# J4.net
KiCad netlist of a schematic drawn in Altium Designer
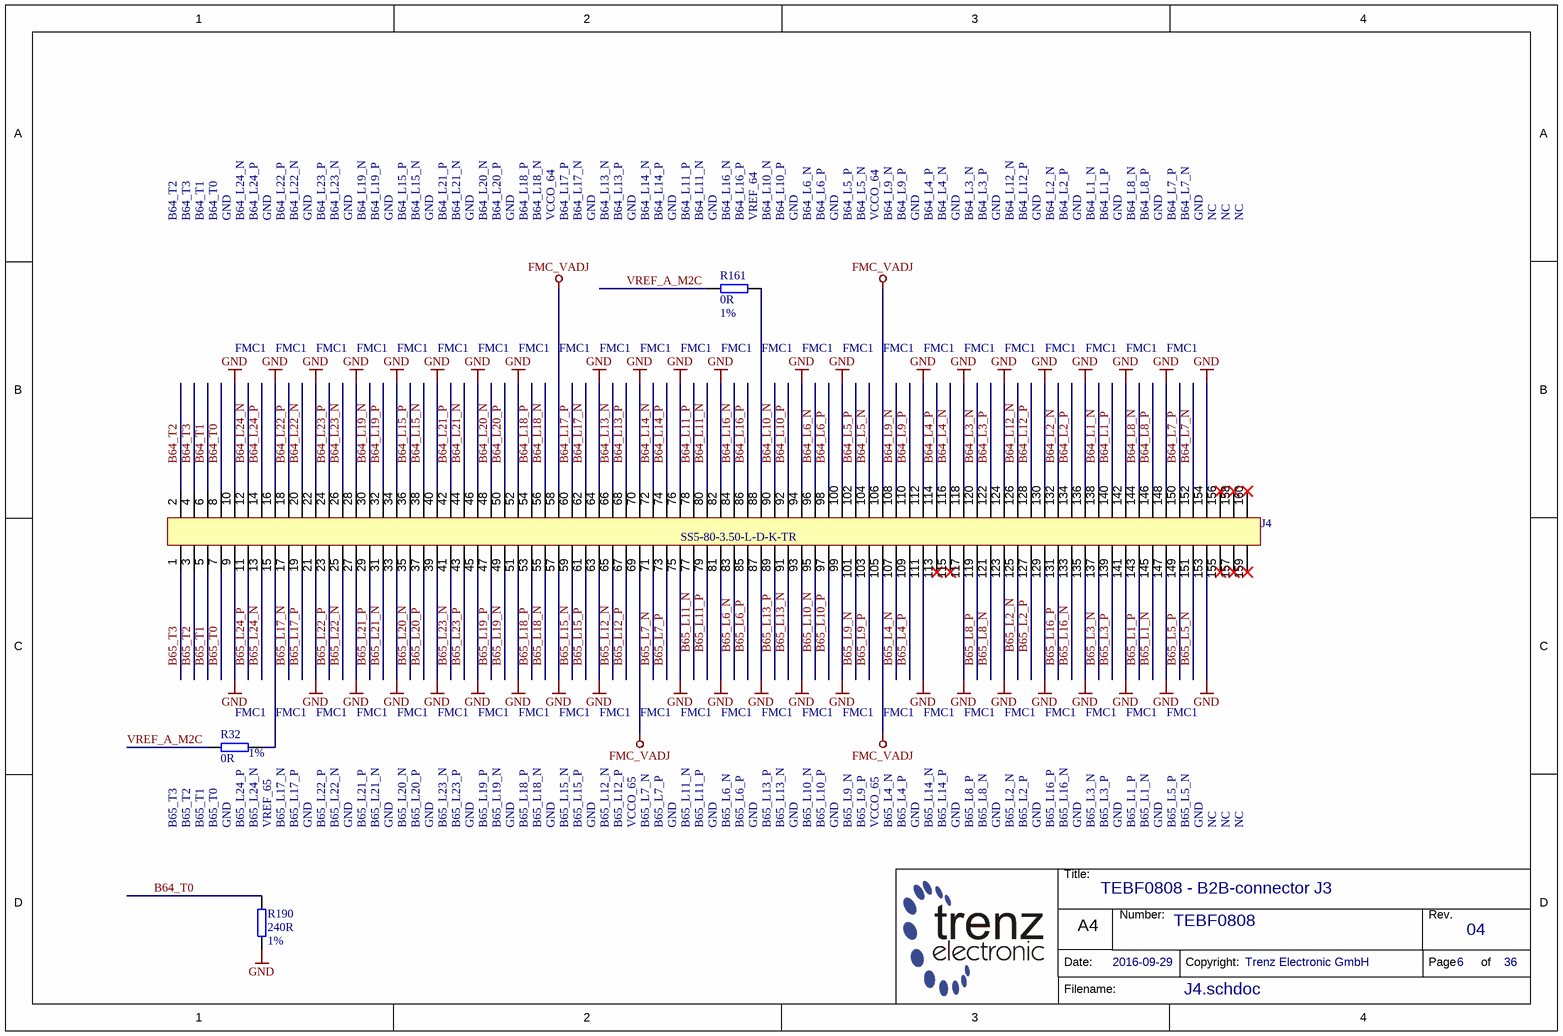
[diagram p0: J4.schdoc]

(export (version "E")
  (design (tool "Eeschema 10.0.6"))
  (components
    (comp (ref "J4")
      (value "SS5-80-3.50-L-D-K-TR")
      (footprint "SS5-80-3.50-L-D-K-TR")
      (description "Samtec Ultra Fine Pitch Socket REF192552-01, 160 Pins")
      (libsource (lib "TE") (part "CON-160"))
    )
    (comp (ref "R32")
      (value "0R")
      (footprint "RESC1005X40N")
      (description "WID SMD 0R")
      (fields (field (name "TOLERANCE") "1%"))
      (libsource (lib "TE") (part "RES"))
    )
    (comp (ref "R161")
      (value "0R")
      (footprint "RESC1005X40N")
      (description "WID SMD 0R")
      (fields (field (name "TOLERANCE") "1%"))
      (libsource (lib "TE") (part "RES"))
    )
    (comp (ref "R190")
      (value "240R")
      (footprint "RESC1005X40N")
      (description "WID SMD 240R 1% 0,063W")
      (fields (field (name "TOLERANCE") "1%"))
      (libsource (lib "TE") (part "RES"))
    )
  )
  (nets
    (net (code "1") (name "/B64_L1_N") (class "Default")
      (node (ref "J4") (pin "138") (pinfunction "138_138") (pintype "passive"))
    )
    (net (code "2") (name "/B64_L1_P") (class "Default")
      (node (ref "J4") (pin "140") (pinfunction "140_140") (pintype "passive"))
    )
    (net (code "3") (name "/B64_L2_N") (class "Default")
      (node (ref "J4") (pin "132") (pinfunction "132_132") (pintype "passive"))
    )
    (net (code "4") (name "/B64_L2_P") (class "Default")
      (node (ref "J4") (pin "134") (pinfunction "134_134") (pintype "passive"))
    )
    (net (code "5") (name "/B64_L3_N") (class "Default")
      (node (ref "J4") (pin "120") (pinfunction "120_120") (pintype "passive"))
    )
    (net (code "6") (name "/B64_L3_P") (class "Default")
      (node (ref "J4") (pin "122") (pinfunction "122_122") (pintype "passive"))
    )
    (net (code "7") (name "/B64_L4_N") (class "Default")
      (node (ref "J4") (pin "116") (pinfunction "116_116") (pintype "passive"))
    )
    (net (code "8") (name "/B64_L4_P") (class "Default")
      (node (ref "J4") (pin "114") (pinfunction "114_114") (pintype "passive"))
    )
    (net (code "9") (name "/B64_L5_N") (class "Default")
      (node (ref "J4") (pin "104") (pinfunction "104_104") (pintype "passive"))
    )
    (net (code "10") (name "/B64_L5_P") (class "Default")
      (node (ref "J4") (pin "102") (pinfunction "102_102") (pintype "passive"))
    )
    (net (code "11") (name "/B64_L6_N") (class "Default")
      (node (ref "J4") (pin "96") (pinfunction "96_96") (pintype "passive"))
    )
    (net (code "12") (name "/B64_L6_P") (class "Default")
      (node (ref "J4") (pin "98") (pinfunction "98_98") (pintype "passive"))
    )
    (net (code "13") (name "/B64_L7_N") (class "Default")
      (node (ref "J4") (pin "152") (pinfunction "152_152") (pintype "passive"))
    )
    (net (code "14") (name "/B64_L7_P") (class "Default")
      (node (ref "J4") (pin "150") (pinfunction "150_150") (pintype "passive"))
    )
    (net (code "15") (name "/B64_L8_N") (class "Default")
      (node (ref "J4") (pin "144") (pinfunction "144_144") (pintype "passive"))
    )
    (net (code "16") (name "/B64_L8_P") (class "Default")
      (node (ref "J4") (pin "146") (pinfunction "146_146") (pintype "passive"))
    )
    (net (code "17") (name "/B64_L9_N") (class "Default")
      (node (ref "J4") (pin "108") (pinfunction "108_108") (pintype "passive"))
    )
    (net (code "18") (name "/B64_L9_P") (class "Default")
      (node (ref "J4") (pin "110") (pinfunction "110_110") (pintype "passive"))
    )
    (net (code "19") (name "/B64_L10_N") (class "Default")
      (node (ref "J4") (pin "90") (pinfunction "90_90") (pintype "passive"))
    )
    (net (code "20") (name "/B64_L10_P") (class "Default")
      (node (ref "J4") (pin "92") (pinfunction "92_92") (pintype "passive"))
    )
    (net (code "21") (name "/B64_L11_N") (class "Default")
      (node (ref "J4") (pin "80") (pinfunction "80_80") (pintype "passive"))
    )
    (net (code "22") (name "/B64_L11_P") (class "Default")
      (node (ref "J4") (pin "78") (pinfunction "78_78") (pintype "passive"))
    )
    (net (code "23") (name "/B64_L12_N") (class "Default")
      (node (ref "J4") (pin "126") (pinfunction "126_126") (pintype "passive"))
    )
    (net (code "24") (name "/B64_L12_P") (class "Default")
      (node (ref "J4") (pin "128") (pinfunction "128_128") (pintype "passive"))
    )
    (net (code "25") (name "/B64_L13_N") (class "Default")
      (node (ref "J4") (pin "66") (pinfunction "66_66") (pintype "passive"))
    )
    (net (code "26") (name "/B64_L13_P") (class "Default")
      (node (ref "J4") (pin "68") (pinfunction "68_68") (pintype "passive"))
    )
    (net (code "27") (name "/B64_L14_N") (class "Default")
      (node (ref "J4") (pin "72") (pinfunction "72_72") (pintype "passive"))
    )
    (net (code "28") (name "/B64_L14_P") (class "Default")
      (node (ref "J4") (pin "74") (pinfunction "74_74") (pintype "passive"))
    )
    (net (code "29") (name "/B64_L15_N") (class "Default")
      (node (ref "J4") (pin "38") (pinfunction "38_38") (pintype "passive"))
    )
    (net (code "30") (name "/B64_L15_P") (class "Default")
      (node (ref "J4") (pin "36") (pinfunction "36_36") (pintype "passive"))
    )
    (net (code "31") (name "/B64_L16_N") (class "Default")
      (node (ref "J4") (pin "84") (pinfunction "84_84") (pintype "passive"))
    )
    (net (code "32") (name "/B64_L16_P") (class "Default")
      (node (ref "J4") (pin "86") (pinfunction "86_86") (pintype "passive"))
    )
    (net (code "33") (name "/B64_L17_N") (class "Default")
      (node (ref "J4") (pin "62") (pinfunction "62_62") (pintype "passive"))
    )
    (net (code "34") (name "/B64_L17_P") (class "Default")
      (node (ref "J4") (pin "60") (pinfunction "60_60") (pintype "passive"))
    )
    (net (code "35") (name "/B64_L18_N") (class "Default")
      (node (ref "J4") (pin "56") (pinfunction "56_56") (pintype "passive"))
    )
    (net (code "36") (name "/B64_L18_P") (class "Default")
      (node (ref "J4") (pin "54") (pinfunction "54_54") (pintype "passive"))
    )
    (net (code "37") (name "/B64_L19_N") (class "Default")
      (node (ref "J4") (pin "30") (pinfunction "30_30") (pintype "passive"))
    )
    (net (code "38") (name "/B64_L19_P") (class "Default")
      (node (ref "J4") (pin "32") (pinfunction "32_32") (pintype "passive"))
    )
    (net (code "39") (name "/B64_L20_N") (class "Default")
      (node (ref "J4") (pin "48") (pinfunction "48_48") (pintype "passive"))
    )
    (net (code "40") (name "/B64_L20_P") (class "Default")
      (node (ref "J4") (pin "50") (pinfunction "50_50") (pintype "passive"))
    )
    (net (code "41") (name "/B64_L21_N") (class "Default")
      (node (ref "J4") (pin "44") (pinfunction "44_44") (pintype "passive"))
    )
    (net (code "42") (name "/B64_L21_P") (class "Default")
      (node (ref "J4") (pin "42") (pinfunction "42_42") (pintype "passive"))
    )
    (net (code "43") (name "/B64_L22_N") (class "Default")
      (node (ref "J4") (pin "20") (pinfunction "20_20") (pintype "passive"))
    )
    (net (code "44") (name "/B64_L22_P") (class "Default")
      (node (ref "J4") (pin "18") (pinfunction "18_18") (pintype "passive"))
    )
    (net (code "45") (name "/B64_L23_N") (class "Default")
      (node (ref "J4") (pin "26") (pinfunction "26_26") (pintype "passive"))
    )
    (net (code "46") (name "/B64_L23_P") (class "Default")
      (node (ref "J4") (pin "24") (pinfunction "24_24") (pintype "passive"))
    )
    (net (code "47") (name "/B64_L24_N") (class "Default")
      (node (ref "J4") (pin "12") (pinfunction "12_12") (pintype "passive"))
    )
    (net (code "48") (name "/B64_L24_P") (class "Default")
      (node (ref "J4") (pin "14") (pinfunction "14_14") (pintype "passive"))
    )
    (net (code "49") (name "/B64_T0") (class "Default")
      (node (ref "J4") (pin "8") (pinfunction "8_8") (pintype "passive"))
      (node (ref "R190") (pin "1") (pinfunction "1_1") (pintype "passive"))
    )
    (net (code "50") (name "/B64_T1") (class "Default")
      (node (ref "J4") (pin "6") (pinfunction "6_6") (pintype "passive"))
    )
    (net (code "51") (name "/B64_T2") (class "Default")
      (node (ref "J4") (pin "2") (pinfunction "2_2") (pintype "passive"))
    )
    (net (code "52") (name "/B64_T3") (class "Default")
      (node (ref "J4") (pin "4") (pinfunction "4_4") (pintype "passive"))
    )
    (net (code "53") (name "/B65_L1_N") (class "Default")
      (node (ref "J4") (pin "145") (pinfunction "145_145") (pintype "passive"))
    )
    (net (code "54") (name "/B65_L1_P") (class "Default")
      (node (ref "J4") (pin "143") (pinfunction "143_143") (pintype "passive"))
    )
    (net (code "55") (name "/B65_L2_N") (class "Default")
      (node (ref "J4") (pin "125") (pinfunction "125_125") (pintype "passive"))
    )
    (net (code "56") (name "/B65_L2_P") (class "Default")
      (node (ref "J4") (pin "127") (pinfunction "127_127") (pintype "passive"))
    )
    (net (code "57") (name "/B65_L3_N") (class "Default")
      (node (ref "J4") (pin "137") (pinfunction "137_137") (pintype "passive"))
    )
    (net (code "58") (name "/B65_L3_P") (class "Default")
      (node (ref "J4") (pin "139") (pinfunction "139_139") (pintype "passive"))
    )
    (net (code "59") (name "/B65_L4_N") (class "Default")
      (node (ref "J4") (pin "107") (pinfunction "107_107") (pintype "passive"))
    )
    (net (code "60") (name "/B65_L4_P") (class "Default")
      (node (ref "J4") (pin "109") (pinfunction "109_109") (pintype "passive"))
    )
    (net (code "61") (name "/B65_L5_N") (class "Default")
      (node (ref "J4") (pin "151") (pinfunction "151_151") (pintype "passive"))
    )
    (net (code "62") (name "/B65_L5_P") (class "Default")
      (node (ref "J4") (pin "149") (pinfunction "149_149") (pintype "passive"))
    )
    (net (code "63") (name "/B65_L6_N") (class "Default")
      (node (ref "J4") (pin "83") (pinfunction "83_83") (pintype "passive"))
    )
    (net (code "64") (name "/B65_L6_P") (class "Default")
      (node (ref "J4") (pin "85") (pinfunction "85_85") (pintype "passive"))
    )
    (net (code "65") (name "/B65_L7_N") (class "Default")
      (node (ref "J4") (pin "71") (pinfunction "71_71") (pintype "passive"))
    )
    (net (code "66") (name "/B65_L7_P") (class "Default")
      (node (ref "J4") (pin "73") (pinfunction "73_73") (pintype "passive"))
    )
    (net (code "67") (name "/B65_L8_N") (class "Default")
      (node (ref "J4") (pin "121") (pinfunction "121_121") (pintype "passive"))
    )
    (net (code "68") (name "/B65_L8_P") (class "Default")
      (node (ref "J4") (pin "119") (pinfunction "119_119") (pintype "passive"))
    )
    (net (code "69") (name "/B65_L9_N") (class "Default")
      (node (ref "J4") (pin "101") (pinfunction "101_101") (pintype "passive"))
    )
    (net (code "70") (name "/B65_L9_P") (class "Default")
      (node (ref "J4") (pin "103") (pinfunction "103_103") (pintype "passive"))
    )
    (net (code "71") (name "/B65_L10_N") (class "Default")
      (node (ref "J4") (pin "95") (pinfunction "95_95") (pintype "passive"))
    )
    (net (code "72") (name "/B65_L10_P") (class "Default")
      (node (ref "J4") (pin "97") (pinfunction "97_97") (pintype "passive"))
    )
    (net (code "73") (name "/B65_L11_N") (class "Default")
      (node (ref "J4") (pin "77") (pinfunction "77_77") (pintype "passive"))
    )
    (net (code "74") (name "/B65_L11_P") (class "Default")
      (node (ref "J4") (pin "79") (pinfunction "79_79") (pintype "passive"))
    )
    (net (code "75") (name "/B65_L12_N") (class "Default")
      (node (ref "J4") (pin "65") (pinfunction "65_65") (pintype "passive"))
    )
    (net (code "76") (name "/B65_L12_P") (class "Default")
      (node (ref "J4") (pin "67") (pinfunction "67_67") (pintype "passive"))
    )
    (net (code "77") (name "/B65_L13_N") (class "Default")
      (node (ref "J4") (pin "91") (pinfunction "91_91") (pintype "passive"))
    )
    (net (code "78") (name "/B65_L13_P") (class "Default")
      (node (ref "J4") (pin "89") (pinfunction "89_89") (pintype "passive"))
    )
    (net (code "79") (name "/B65_L15_N") (class "Default")
      (node (ref "J4") (pin "59") (pinfunction "59_59") (pintype "passive"))
    )
    (net (code "80") (name "/B65_L15_P") (class "Default")
      (node (ref "J4") (pin "61") (pinfunction "61_61") (pintype "passive"))
    )
    (net (code "81") (name "/B65_L16_N") (class "Default")
      (node (ref "J4") (pin "133") (pinfunction "133_133") (pintype "passive"))
    )
    (net (code "82") (name "/B65_L16_P") (class "Default")
      (node (ref "J4") (pin "131") (pinfunction "131_131") (pintype "passive"))
    )
    (net (code "83") (name "/B65_L17_N") (class "Default")
      (node (ref "J4") (pin "17") (pinfunction "17_17") (pintype "passive"))
    )
    (net (code "84") (name "/B65_L17_P") (class "Default")
      (node (ref "J4") (pin "19") (pinfunction "19_19") (pintype "passive"))
    )
    (net (code "85") (name "/B65_L18_N") (class "Default")
      (node (ref "J4") (pin "55") (pinfunction "55_55") (pintype "passive"))
    )
    (net (code "86") (name "/B65_L18_P") (class "Default")
      (node (ref "J4") (pin "53") (pinfunction "53_53") (pintype "passive"))
    )
    (net (code "87") (name "/B65_L19_N") (class "Default")
      (node (ref "J4") (pin "49") (pinfunction "49_49") (pintype "passive"))
    )
    (net (code "88") (name "/B65_L19_P") (class "Default")
      (node (ref "J4") (pin "47") (pinfunction "47_47") (pintype "passive"))
    )
    (net (code "89") (name "/B65_L20_N") (class "Default")
      (node (ref "J4") (pin "35") (pinfunction "35_35") (pintype "passive"))
    )
    (net (code "90") (name "/B65_L20_P") (class "Default")
      (node (ref "J4") (pin "37") (pinfunction "37_37") (pintype "passive"))
    )
    (net (code "91") (name "/B65_L21_N") (class "Default")
      (node (ref "J4") (pin "31") (pinfunction "31_31") (pintype "passive"))
    )
    (net (code "92") (name "/B65_L21_P") (class "Default")
      (node (ref "J4") (pin "29") (pinfunction "29_29") (pintype "passive"))
    )
    (net (code "93") (name "/B65_L22_N") (class "Default")
      (node (ref "J4") (pin "25") (pinfunction "25_25") (pintype "passive"))
    )
    (net (code "94") (name "/B65_L22_P") (class "Default")
      (node (ref "J4") (pin "23") (pinfunction "23_23") (pintype "passive"))
    )
    (net (code "95") (name "/B65_L23_N") (class "Default")
      (node (ref "J4") (pin "41") (pinfunction "41_41") (pintype "passive"))
    )
    (net (code "96") (name "/B65_L23_P") (class "Default")
      (node (ref "J4") (pin "43") (pinfunction "43_43") (pintype "passive"))
    )
    (net (code "97") (name "/B65_L24_N") (class "Default")
      (node (ref "J4") (pin "13") (pinfunction "13_13") (pintype "passive"))
    )
    (net (code "98") (name "/B65_L24_P") (class "Default")
      (node (ref "J4") (pin "11") (pinfunction "11_11") (pintype "passive"))
    )
    (net (code "99") (name "/B65_T0") (class "Default")
      (node (ref "J4") (pin "7") (pinfunction "7_7") (pintype "passive"))
    )
    (net (code "100") (name "/B65_T1") (class "Default")
      (node (ref "J4") (pin "5") (pinfunction "5_5") (pintype "passive"))
    )
    (net (code "101") (name "/B65_T2") (class "Default")
      (node (ref "J4") (pin "3") (pinfunction "3_3") (pintype "passive"))
    )
    (net (code "102") (name "/B65_T3") (class "Default")
      (node (ref "J4") (pin "1") (pinfunction "1_1") (pintype "passive"))
    )
    (net (code "103") (name "/VREF_A_M2C") (class "Default")
      (node (ref "R161") (pin "1") (pinfunction "1_1") (pintype "passive"))
      (node (ref "R32") (pin "2") (pinfunction "2_2") (pintype "passive"))
    )
    (net (code "104") (name "FMC_VADJ") (class "Default")
      (node (ref "J4") (pin "105") (pinfunction "105_105") (pintype "passive"))
      (node (ref "J4") (pin "106") (pinfunction "106_106") (pintype "passive"))
      (node (ref "J4") (pin "58") (pinfunction "58_58") (pintype "passive"))
      (node (ref "J4") (pin "69") (pinfunction "69_69") (pintype "passive"))
    )
    (net (code "105") (name "GND") (class "Default")
      (node (ref "J4") (pin "10") (pinfunction "10_10") (pintype "passive"))
      (node (ref "J4") (pin "100") (pinfunction "100_100") (pintype "passive"))
      (node (ref "J4") (pin "111") (pinfunction "111_111") (pintype "passive"))
      (node (ref "J4") (pin "112") (pinfunction "112_112") (pintype "passive"))
      (node (ref "J4") (pin "117") (pinfunction "117_117") (pintype "passive"))
      (node (ref "J4") (pin "118") (pinfunction "118_118") (pintype "passive"))
      (node (ref "J4") (pin "123") (pinfunction "123_123") (pintype "passive"))
      (node (ref "J4") (pin "124") (pinfunction "124_124") (pintype "passive"))
      (node (ref "J4") (pin "129") (pinfunction "129_129") (pintype "passive"))
      (node (ref "J4") (pin "130") (pinfunction "130_130") (pintype "passive"))
      (node (ref "J4") (pin "135") (pinfunction "135_135") (pintype "passive"))
      (node (ref "J4") (pin "136") (pinfunction "136_136") (pintype "passive"))
      (node (ref "J4") (pin "141") (pinfunction "141_141") (pintype "passive"))
      (node (ref "J4") (pin "142") (pinfunction "142_142") (pintype "passive"))
      (node (ref "J4") (pin "147") (pinfunction "147_147") (pintype "passive"))
      (node (ref "J4") (pin "148") (pinfunction "148_148") (pintype "passive"))
      (node (ref "J4") (pin "153") (pinfunction "153_153") (pintype "passive"))
      (node (ref "J4") (pin "154") (pinfunction "154_154") (pintype "passive"))
      (node (ref "J4") (pin "16") (pinfunction "16_16") (pintype "passive"))
      (node (ref "J4") (pin "21") (pinfunction "21_21") (pintype "passive"))
      (node (ref "J4") (pin "22") (pinfunction "22_22") (pintype "passive"))
      (node (ref "J4") (pin "27") (pinfunction "27_27") (pintype "passive"))
      (node (ref "J4") (pin "28") (pinfunction "28_28") (pintype "passive"))
      (node (ref "J4") (pin "33") (pinfunction "33_33") (pintype "passive"))
      (node (ref "J4") (pin "34") (pinfunction "34_34") (pintype "passive"))
      (node (ref "J4") (pin "39") (pinfunction "39_39") (pintype "passive"))
      (node (ref "J4") (pin "40") (pinfunction "40_40") (pintype "passive"))
      (node (ref "J4") (pin "45") (pinfunction "45_45") (pintype "passive"))
      (node (ref "J4") (pin "46") (pinfunction "46_46") (pintype "passive"))
      (node (ref "J4") (pin "51") (pinfunction "51_51") (pintype "passive"))
      (node (ref "J4") (pin "52") (pinfunction "52_52") (pintype "passive"))
      (node (ref "J4") (pin "57") (pinfunction "57_57") (pintype "passive"))
      (node (ref "J4") (pin "63") (pinfunction "63_63") (pintype "passive"))
      (node (ref "J4") (pin "64") (pinfunction "64_64") (pintype "passive"))
      (node (ref "J4") (pin "70") (pinfunction "70_70") (pintype "passive"))
      (node (ref "J4") (pin "75") (pinfunction "75_75") (pintype "passive"))
      (node (ref "J4") (pin "76") (pinfunction "76_76") (pintype "passive"))
      (node (ref "J4") (pin "81") (pinfunction "81_81") (pintype "passive"))
      (node (ref "J4") (pin "82") (pinfunction "82_82") (pintype "passive"))
      (node (ref "J4") (pin "87") (pinfunction "87_87") (pintype "passive"))
      (node (ref "J4") (pin "9") (pinfunction "9_9") (pintype "passive"))
      (node (ref "J4") (pin "93") (pinfunction "93_93") (pintype "passive"))
      (node (ref "J4") (pin "94") (pinfunction "94_94") (pintype "passive"))
      (node (ref "J4") (pin "99") (pinfunction "99_99") (pintype "passive"))
      (node (ref "R190") (pin "2") (pinfunction "2_2") (pintype "passive"))
    )
    (net (code "106") (name "Net-(J4-Pad15)") (class "Default")
      (node (ref "J4") (pin "15") (pinfunction "15_15") (pintype "passive"))
      (node (ref "R32") (pin "1") (pinfunction "1_1") (pintype "passive"))
    )
    (net (code "107") (name "Net-(J4-Pad88)") (class "Default")
      (node (ref "J4") (pin "88") (pinfunction "88_88") (pintype "passive"))
      (node (ref "R161") (pin "2") (pinfunction "2_2") (pintype "passive"))
    )
    (net (code "108") (name "unconnected-(J4-Pad113)") (class "Default")
      (node (ref "J4") (pin "113") (pinfunction "113_113") (pintype "passive+no_connect"))
    )
    (net (code "109") (name "unconnected-(J4-Pad115)") (class "Default")
      (node (ref "J4") (pin "115") (pinfunction "115_115") (pintype "passive+no_connect"))
    )
    (net (code "110") (name "unconnected-(J4-Pad155)") (class "Default")
      (node (ref "J4") (pin "155") (pinfunction "155_155") (pintype "passive+no_connect"))
    )
    (net (code "111") (name "unconnected-(J4-Pad156)") (class "Default")
      (node (ref "J4") (pin "156") (pinfunction "156_156") (pintype "passive+no_connect"))
    )
    (net (code "112") (name "unconnected-(J4-Pad157)") (class "Default")
      (node (ref "J4") (pin "157") (pinfunction "157_157") (pintype "passive+no_connect"))
    )
    (net (code "113") (name "unconnected-(J4-Pad158)") (class "Default")
      (node (ref "J4") (pin "158") (pinfunction "158_158") (pintype "passive+no_connect"))
    )
    (net (code "114") (name "unconnected-(J4-Pad159)") (class "Default")
      (node (ref "J4") (pin "159") (pinfunction "159_159") (pintype "passive+no_connect"))
    )
    (net (code "115") (name "unconnected-(J4-Pad160)") (class "Default")
      (node (ref "J4") (pin "160") (pinfunction "160_160") (pintype "passive+no_connect"))
    )
  )
)
